# control_bdr.net
KiCad netlist of a schematic drawn in EAGLE
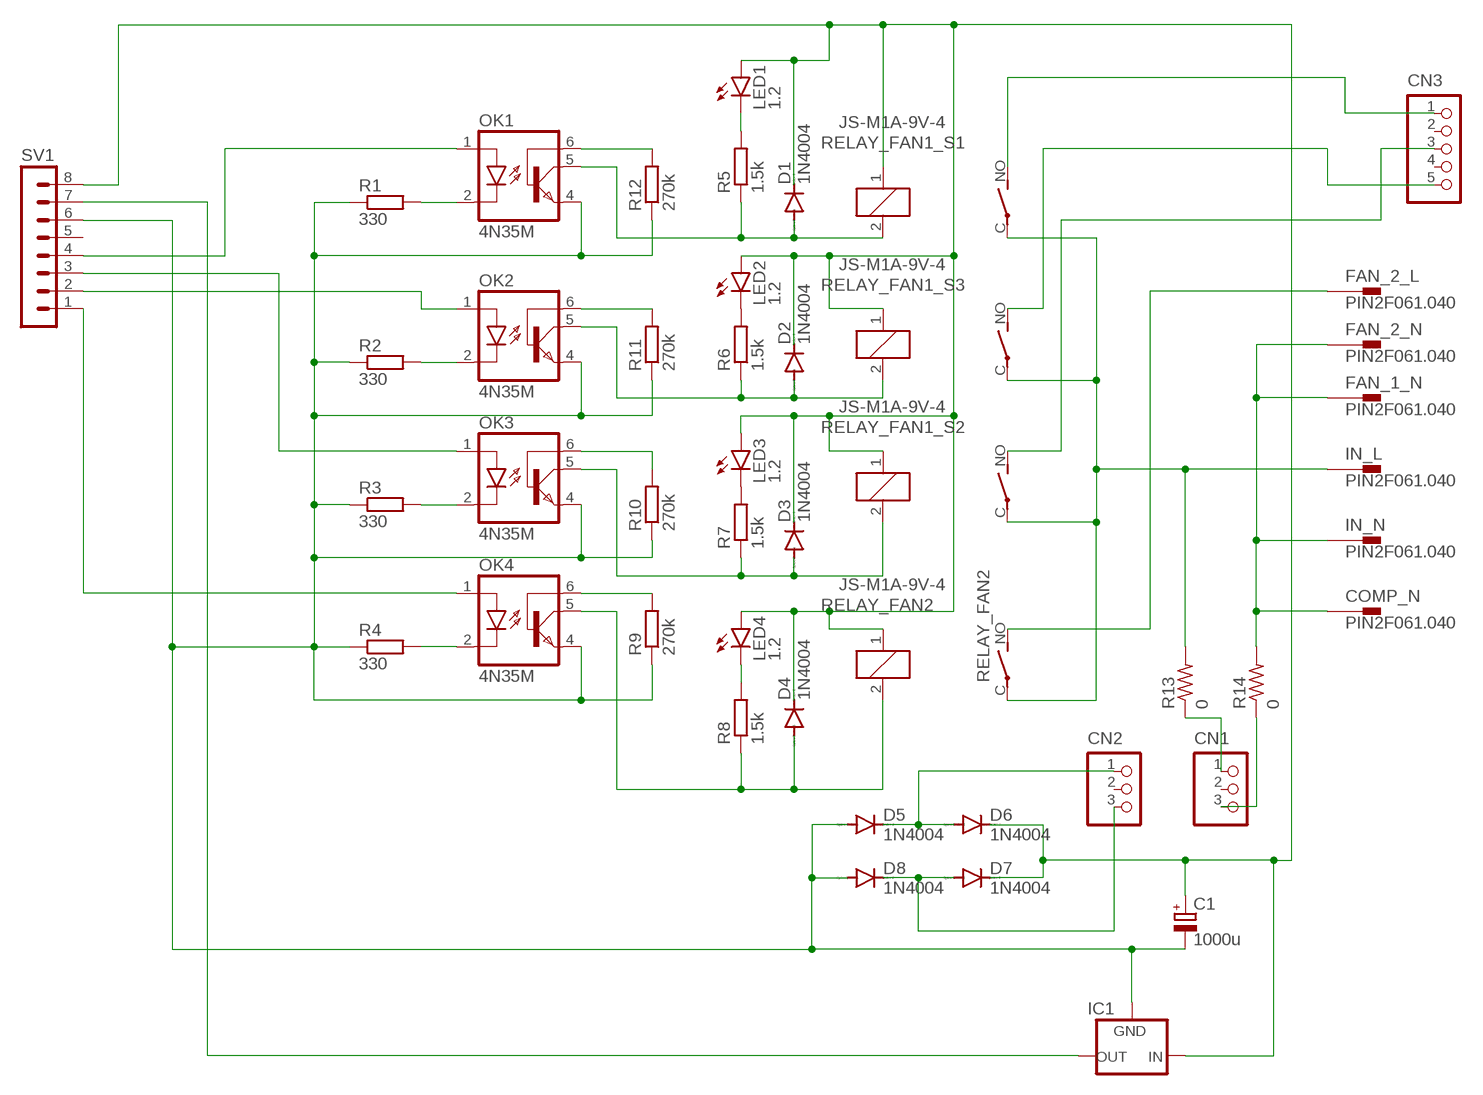
[diagram p0: schematic, sheet 1]

(export (version "E")
  (design (tool "Eeschema 10.0.6"))
  (components
    (comp (ref "C1")
      (value "1000u")
      (footprint "eagle-import:E3,5-10")
      (libsource (lib "eagle-import") (part "CPOL-EUE3.5-10"))
    )
    (comp (ref "CN1")
      (value "B3P-VH")
      (footprint "eagle-import:B3P-VH")
      (libsource (lib "eagle-import") (part "B3P-VH"))
    )
    (comp (ref "CN2")
      (value "B3B-XASK-1")
      (footprint "eagle-import:B3B-XASK-1")
      (libsource (lib "eagle-import") (part "B3B-XASK-1"))
    )
    (comp (ref "CN3")
      (value "B5P-VH")
      (footprint "eagle-import:B5P-VH")
      (libsource (lib "eagle-import") (part "B5P-VH"))
    )
    (comp (ref "COMP_N")
      (value "PIN2F061.040")
      (footprint "eagle-import:F061.040")
      (libsource (lib "eagle-import") (part "PIN2F061.040"))
    )
    (comp (ref "D1")
      (value "1N4004")
      (footprint "eagle-import:DO41-10")
      (libsource (lib "eagle-import") (part "1N4004"))
    )
    (comp (ref "D2")
      (value "1N4004")
      (footprint "eagle-import:DO41-10")
      (libsource (lib "eagle-import") (part "1N4004"))
    )
    (comp (ref "D3")
      (value "1N4004")
      (footprint "eagle-import:DO41-10")
      (libsource (lib "eagle-import") (part "1N4004"))
    )
    (comp (ref "D4")
      (value "1N4004")
      (footprint "eagle-import:DO41-10")
      (libsource (lib "eagle-import") (part "1N4004"))
    )
    (comp (ref "D5")
      (value "1N4004")
      (footprint "eagle-import:DO41-10")
      (libsource (lib "eagle-import") (part "1N4004"))
    )
    (comp (ref "D6")
      (value "1N4004")
      (footprint "eagle-import:DO41-10")
      (libsource (lib "eagle-import") (part "1N4004"))
    )
    (comp (ref "D7")
      (value "1N4004")
      (footprint "eagle-import:DO41-10")
      (libsource (lib "eagle-import") (part "1N4004"))
    )
    (comp (ref "D8")
      (value "1N4004")
      (footprint "eagle-import:DO41-10")
      (libsource (lib "eagle-import") (part "1N4004"))
    )
    (comp (ref "FAN_1_N")
      (value "PIN2F061.040")
      (footprint "eagle-import:F061.040")
      (libsource (lib "eagle-import") (part "PIN2F061.040"))
    )
    (comp (ref "FAN_2_L")
      (value "PIN2F061.040")
      (footprint "eagle-import:F061.040")
      (libsource (lib "eagle-import") (part "PIN2F061.040"))
    )
    (comp (ref "FAN_2_N")
      (value "PIN2F061.040")
      (footprint "eagle-import:F061.040")
      (libsource (lib "eagle-import") (part "PIN2F061.040"))
    )
    (comp (ref "IC1")
      (value "78XXL")
      (footprint "eagle-import:78XXL")
      (libsource (lib "eagle-import") (part "78XXL"))
    )
    (comp (ref "IN_L")
      (value "PIN2F061.040")
      (footprint "eagle-import:F061.040")
      (libsource (lib "eagle-import") (part "PIN2F061.040"))
    )
    (comp (ref "IN_N")
      (value "PIN2F061.040")
      (footprint "eagle-import:F061.040")
      (libsource (lib "eagle-import") (part "PIN2F061.040"))
    )
    (comp (ref "LED1")
      (value "1.2")
      (footprint "eagle-import:LED5MM")
      (libsource (lib "eagle-import") (part "LED5MM"))
    )
    (comp (ref "LED2")
      (value "1.2")
      (footprint "eagle-import:LED5MM")
      (libsource (lib "eagle-import") (part "LED5MM"))
    )
    (comp (ref "LED3")
      (value "1.2")
      (footprint "eagle-import:LED5MM")
      (libsource (lib "eagle-import") (part "LED5MM"))
    )
    (comp (ref "LED4")
      (value "1.2")
      (footprint "eagle-import:LED5MM")
      (libsource (lib "eagle-import") (part "LED5MM"))
    )
    (comp (ref "OK1")
      (value "4N35M")
      (footprint "eagle-import:DIL06")
      (fields (field (name "MPN") "4N35-M"))
      (libsource (lib "eagle-import") (part "4N?M35"))
    )
    (comp (ref "OK2")
      (value "4N35M")
      (footprint "eagle-import:DIL06")
      (fields (field (name "MPN") "4N35-M"))
      (libsource (lib "eagle-import") (part "4N?M35"))
    )
    (comp (ref "OK3")
      (value "4N35M")
      (footprint "eagle-import:DIL06")
      (fields (field (name "MPN") "4N35-M"))
      (libsource (lib "eagle-import") (part "4N?M35"))
    )
    (comp (ref "OK4")
      (value "4N35M")
      (footprint "eagle-import:DIL06")
      (fields (field (name "MPN") "4N35-M"))
      (libsource (lib "eagle-import") (part "4N?M35"))
    )
    (comp (ref "R1")
      (value "330")
      (footprint "eagle-import:0204_7")
      (libsource (lib "eagle-import") (part "R-EU_0204/7"))
    )
    (comp (ref "R2")
      (value "330")
      (footprint "eagle-import:0204_7")
      (libsource (lib "eagle-import") (part "R-EU_0204/7"))
    )
    (comp (ref "R3")
      (value "330")
      (footprint "eagle-import:0204_7")
      (libsource (lib "eagle-import") (part "R-EU_0204/7"))
    )
    (comp (ref "R4")
      (value "330")
      (footprint "eagle-import:0204_7")
      (libsource (lib "eagle-import") (part "R-EU_0204/7"))
    )
    (comp (ref "R5")
      (value "1.5k")
      (footprint "eagle-import:0204_7")
      (libsource (lib "eagle-import") (part "R-EU_0204/7"))
    )
    (comp (ref "R6")
      (value "1.5k")
      (footprint "eagle-import:0204_7")
      (libsource (lib "eagle-import") (part "R-EU_0204/7"))
    )
    (comp (ref "R7")
      (value "1.5k")
      (footprint "eagle-import:0204_7")
      (libsource (lib "eagle-import") (part "R-EU_0204/7"))
    )
    (comp (ref "R8")
      (value "1.5k")
      (footprint "eagle-import:0204_7")
      (libsource (lib "eagle-import") (part "R-EU_0204/7"))
    )
    (comp (ref "R9")
      (value "270k")
      (footprint "eagle-import:0204_7")
      (libsource (lib "eagle-import") (part "R-EU_0204/7"))
    )
    (comp (ref "R10")
      (value "270k")
      (footprint "eagle-import:0204_7")
      (libsource (lib "eagle-import") (part "R-EU_0204/7"))
    )
    (comp (ref "R11")
      (value "270k")
      (footprint "eagle-import:0204_7")
      (libsource (lib "eagle-import") (part "R-EU_0204/7"))
    )
    (comp (ref "R12")
      (value "270k")
      (footprint "eagle-import:0204_7")
      (libsource (lib "eagle-import") (part "R-EU_0204/7"))
    )
    (comp (ref "R13")
      (value "0")
      (footprint "eagle-import:0204V")
      (libsource (lib "eagle-import") (part "R-US_0204/2V"))
    )
    (comp (ref "R14")
      (value "0")
      (footprint "eagle-import:0204V")
      (libsource (lib "eagle-import") (part "R-US_0204/2V"))
    )
    (comp (ref "RELAY_FAN1_S1")
      (value "JS-M1A-9V-4")
      (footprint "eagle-import:JS-M1A")
      (libsource (lib "eagle-import") (part "JS-M1A-9V-4"))
    )
    (comp (ref "RELAY_FAN1_S2")
      (value "JS-M1A-9V-4")
      (footprint "eagle-import:JS-M1A")
      (libsource (lib "eagle-import") (part "JS-M1A-9V-4"))
    )
    (comp (ref "RELAY_FAN1_S3")
      (value "JS-M1A-9V-4")
      (footprint "eagle-import:JS-M1A")
      (libsource (lib "eagle-import") (part "JS-M1A-9V-4"))
    )
    (comp (ref "RELAY_FAN2")
      (value "JS-M1A-9V-4")
      (footprint "eagle-import:JS-M1A")
      (libsource (lib "eagle-import") (part "JS-M1A-9V-4"))
    )
    (comp (ref "SV1")
      (value "MA08-1")
      (footprint "eagle-import:MA08-1")
      (libsource (lib "eagle-import") (part "MA08-1"))
    )
  )
  (nets
    (net (code "1") (name "Net-(C1-Pad+)") (class "Default")
      (node (ref "C1") (pin "+") (pinfunction "+_+") (pintype "passive"))
      (node (ref "D1") (pin "C") (pinfunction "C_C") (pintype "passive"))
      (node (ref "D2") (pin "C") (pinfunction "C_C") (pintype "passive"))
      (node (ref "D3") (pin "C") (pinfunction "C_C") (pintype "passive"))
      (node (ref "D4") (pin "C") (pinfunction "C_C") (pintype "passive"))
      (node (ref "D6") (pin "C") (pinfunction "C_C") (pintype "passive"))
      (node (ref "D7") (pin "C") (pinfunction "C_C") (pintype "passive"))
      (node (ref "IC1") (pin "IN") (pinfunction "IN_IN") (pintype "input"))
      (node (ref "LED1") (pin "A") (pinfunction "A_A") (pintype "passive"))
      (node (ref "LED2") (pin "A") (pinfunction "A_A") (pintype "passive"))
      (node (ref "LED3") (pin "A") (pinfunction "A_A") (pintype "passive"))
      (node (ref "LED4") (pin "A") (pinfunction "A_A") (pintype "passive"))
      (node (ref "RELAY_FAN1_S1") (pin "1") (pinfunction "1_1") (pintype "passive"))
      (node (ref "RELAY_FAN1_S2") (pin "1") (pinfunction "1_1") (pintype "passive"))
      (node (ref "RELAY_FAN1_S3") (pin "1") (pinfunction "1_1") (pintype "passive"))
      (node (ref "RELAY_FAN2") (pin "1") (pinfunction "1_1") (pintype "passive"))
      (node (ref "SV1") (pin "8") (pinfunction "8_8") (pintype "passive"))
    )
    (net (code "2") (name "Net-(CN1-Pad1)") (class "Default")
      (node (ref "CN1") (pin "1") (pinfunction "1_1") (pintype "passive"))
      (node (ref "R13") (pin "1") (pinfunction "1_1") (pintype "passive"))
    )
    (net (code "3") (name "Net-(CN1-Pad3)") (class "Default")
      (node (ref "CN1") (pin "3") (pinfunction "3_3") (pintype "passive"))
      (node (ref "R14") (pin "1") (pinfunction "1_1") (pintype "passive"))
    )
    (net (code "4") (name "Net-(CN2-Pad1)") (class "Default")
      (node (ref "CN2") (pin "1") (pinfunction "1_1") (pintype "passive"))
      (node (ref "D5") (pin "C") (pinfunction "C_C") (pintype "passive"))
      (node (ref "D6") (pin "A") (pinfunction "A_A") (pintype "passive"))
    )
    (net (code "5") (name "Net-(CN2-Pad3)") (class "Default")
      (node (ref "CN2") (pin "3") (pinfunction "3_3") (pintype "passive"))
      (node (ref "D7") (pin "A") (pinfunction "A_A") (pintype "passive"))
      (node (ref "D8") (pin "C") (pinfunction "C_C") (pintype "passive"))
    )
    (net (code "6") (name "Net-(COMP_N-1-PadA1)") (class "Default")
      (node (ref "COMP_N") (pin "A1") (pinfunction "1_A1") (pintype "passive"))
      (node (ref "COMP_N") (pin "A2") (pinfunction "1_A2") (pintype "passive"))
      (node (ref "FAN_1_N") (pin "A1") (pinfunction "1_A1") (pintype "passive"))
      (node (ref "FAN_1_N") (pin "A2") (pinfunction "1_A2") (pintype "passive"))
      (node (ref "FAN_2_N") (pin "A1") (pinfunction "1_A1") (pintype "passive"))
      (node (ref "FAN_2_N") (pin "A2") (pinfunction "1_A2") (pintype "passive"))
      (node (ref "IN_N") (pin "A1") (pinfunction "1_A1") (pintype "passive"))
      (node (ref "IN_N") (pin "A2") (pinfunction "1_A2") (pintype "passive"))
      (node (ref "R14") (pin "2") (pinfunction "2_2") (pintype "passive"))
    )
    (net (code "7") (name "Net-(IC1-PadOUT)") (class "Default")
      (node (ref "IC1") (pin "OUT") (pinfunction "OUT_OUT") (pintype "passive"))
      (node (ref "SV1") (pin "7") (pinfunction "7_7") (pintype "passive"))
    )
    (net (code "8") (name "Net-(LED1-C)") (class "Default")
      (node (ref "LED1") (pin "K") (pinfunction "C_K") (pintype "passive"))
      (node (ref "R5") (pin "2") (pinfunction "2_2") (pintype "passive"))
    )
    (net (code "9") (name "Net-(LED2-C)") (class "Default")
      (node (ref "LED2") (pin "K") (pinfunction "C_K") (pintype "passive"))
      (node (ref "R6") (pin "2") (pinfunction "2_2") (pintype "passive"))
    )
    (net (code "10") (name "Net-(LED3-C)") (class "Default")
      (node (ref "LED3") (pin "K") (pinfunction "C_K") (pintype "passive"))
      (node (ref "R7") (pin "2") (pinfunction "2_2") (pintype "passive"))
    )
    (net (code "11") (name "Net-(LED4-C)") (class "Default")
      (node (ref "LED4") (pin "K") (pinfunction "C_K") (pintype "passive"))
      (node (ref "R8") (pin "2") (pinfunction "2_2") (pintype "passive"))
    )
    (net (code "12") (name "Net-(OK1-A)") (class "Default")
      (node (ref "OK1") (pin "1") (pinfunction "A_1") (pintype "passive"))
      (node (ref "SV1") (pin "4") (pinfunction "4_4") (pintype "passive"))
    )
    (net (code "13") (name "Net-(OK1-BAS)") (class "Default")
      (node (ref "OK1") (pin "6") (pinfunction "BAS_6") (pintype "passive"))
      (node (ref "R12") (pin "2") (pinfunction "2_2") (pintype "passive"))
    )
    (net (code "14") (name "Net-(OK1-C)") (class "Default")
      (node (ref "OK1") (pin "2") (pinfunction "C_2") (pintype "passive"))
      (node (ref "R1") (pin "2") (pinfunction "2_2") (pintype "passive"))
    )
    (net (code "15") (name "Net-(OK1-COL)") (class "Default")
      (node (ref "D1") (pin "A") (pinfunction "A_A") (pintype "passive"))
      (node (ref "OK1") (pin "5") (pinfunction "COL_5") (pintype "passive"))
      (node (ref "R5") (pin "1") (pinfunction "1_1") (pintype "passive"))
      (node (ref "RELAY_FAN1_S1") (pin "2") (pinfunction "2_2") (pintype "passive"))
    )
    (net (code "16") (name "Net-(OK1-EMI)") (class "Default")
      (node (ref "C1") (pin "-") (pinfunction "-_-") (pintype "passive"))
      (node (ref "D5") (pin "A") (pinfunction "A_A") (pintype "passive"))
      (node (ref "D8") (pin "A") (pinfunction "A_A") (pintype "passive"))
      (node (ref "IC1") (pin "GND") (pinfunction "GND_GND") (pintype "input"))
      (node (ref "OK1") (pin "4") (pinfunction "EMI_4") (pintype "passive"))
      (node (ref "OK2") (pin "4") (pinfunction "EMI_4") (pintype "passive"))
      (node (ref "OK3") (pin "4") (pinfunction "EMI_4") (pintype "passive"))
      (node (ref "OK4") (pin "4") (pinfunction "EMI_4") (pintype "passive"))
      (node (ref "R1") (pin "1") (pinfunction "1_1") (pintype "passive"))
      (node (ref "R10") (pin "1") (pinfunction "1_1") (pintype "passive"))
      (node (ref "R11") (pin "1") (pinfunction "1_1") (pintype "passive"))
      (node (ref "R12") (pin "1") (pinfunction "1_1") (pintype "passive"))
      (node (ref "R2") (pin "1") (pinfunction "1_1") (pintype "passive"))
      (node (ref "R3") (pin "1") (pinfunction "1_1") (pintype "passive"))
      (node (ref "R4") (pin "1") (pinfunction "1_1") (pintype "passive"))
      (node (ref "R9") (pin "1") (pinfunction "1_1") (pintype "passive"))
      (node (ref "SV1") (pin "6") (pinfunction "6_6") (pintype "passive"))
    )
    (net (code "17") (name "Net-(OK2-A)") (class "Default")
      (node (ref "OK2") (pin "1") (pinfunction "A_1") (pintype "passive"))
      (node (ref "SV1") (pin "2") (pinfunction "2_2") (pintype "passive"))
    )
    (net (code "18") (name "Net-(OK2-BAS)") (class "Default")
      (node (ref "OK2") (pin "6") (pinfunction "BAS_6") (pintype "passive"))
      (node (ref "R11") (pin "2") (pinfunction "2_2") (pintype "passive"))
    )
    (net (code "19") (name "Net-(OK2-C)") (class "Default")
      (node (ref "OK2") (pin "2") (pinfunction "C_2") (pintype "passive"))
      (node (ref "R2") (pin "2") (pinfunction "2_2") (pintype "passive"))
    )
    (net (code "20") (name "Net-(OK2-COL)") (class "Default")
      (node (ref "D2") (pin "A") (pinfunction "A_A") (pintype "passive"))
      (node (ref "OK2") (pin "5") (pinfunction "COL_5") (pintype "passive"))
      (node (ref "R6") (pin "1") (pinfunction "1_1") (pintype "passive"))
      (node (ref "RELAY_FAN1_S3") (pin "2") (pinfunction "2_2") (pintype "passive"))
    )
    (net (code "21") (name "Net-(OK3-A)") (class "Default")
      (node (ref "OK3") (pin "1") (pinfunction "A_1") (pintype "passive"))
      (node (ref "SV1") (pin "3") (pinfunction "3_3") (pintype "passive"))
    )
    (net (code "22") (name "Net-(OK3-BAS)") (class "Default")
      (node (ref "OK3") (pin "6") (pinfunction "BAS_6") (pintype "passive"))
      (node (ref "R10") (pin "2") (pinfunction "2_2") (pintype "passive"))
    )
    (net (code "23") (name "Net-(OK3-C)") (class "Default")
      (node (ref "OK3") (pin "2") (pinfunction "C_2") (pintype "passive"))
      (node (ref "R3") (pin "2") (pinfunction "2_2") (pintype "passive"))
    )
    (net (code "24") (name "Net-(OK3-COL)") (class "Default")
      (node (ref "D3") (pin "A") (pinfunction "A_A") (pintype "passive"))
      (node (ref "OK3") (pin "5") (pinfunction "COL_5") (pintype "passive"))
      (node (ref "R7") (pin "1") (pinfunction "1_1") (pintype "passive"))
      (node (ref "RELAY_FAN1_S2") (pin "2") (pinfunction "2_2") (pintype "passive"))
    )
    (net (code "25") (name "Net-(OK4-A)") (class "Default")
      (node (ref "OK4") (pin "1") (pinfunction "A_1") (pintype "passive"))
      (node (ref "SV1") (pin "1") (pinfunction "1_1") (pintype "passive"))
    )
    (net (code "26") (name "Net-(OK4-BAS)") (class "Default")
      (node (ref "OK4") (pin "6") (pinfunction "BAS_6") (pintype "passive"))
      (node (ref "R9") (pin "2") (pinfunction "2_2") (pintype "passive"))
    )
    (net (code "27") (name "Net-(OK4-C)") (class "Default")
      (node (ref "OK4") (pin "2") (pinfunction "C_2") (pintype "passive"))
      (node (ref "R4") (pin "2") (pinfunction "2_2") (pintype "passive"))
    )
    (net (code "28") (name "Net-(OK4-COL)") (class "Default")
      (node (ref "D4") (pin "A") (pinfunction "A_A") (pintype "passive"))
      (node (ref "OK4") (pin "5") (pinfunction "COL_5") (pintype "passive"))
      (node (ref "R8") (pin "1") (pinfunction "1_1") (pintype "passive"))
      (node (ref "RELAY_FAN2") (pin "2") (pinfunction "2_2") (pintype "passive"))
    )
    (net (code "29") (name "Net-(RELAY_FAN1_S1B-P)") (class "Default")
      (node (ref "IN_L") (pin "A1") (pinfunction "1_A1") (pintype "passive"))
      (node (ref "IN_L") (pin "A2") (pinfunction "1_A2") (pintype "passive"))
      (node (ref "R13") (pin "2") (pinfunction "2_2") (pintype "passive"))
      (node (ref "RELAY_FAN1_S1") (pin "C") (pinfunction "P_C") (pintype "passive"))
      (node (ref "RELAY_FAN1_S2") (pin "C") (pinfunction "P_C") (pintype "passive"))
      (node (ref "RELAY_FAN1_S3") (pin "C") (pinfunction "P_C") (pintype "passive"))
      (node (ref "RELAY_FAN2") (pin "C") (pinfunction "P_C") (pintype "passive"))
    )
    (net (code "30") (name "Net-(RELAY_FAN1_S1B-S)") (class "Default")
      (node (ref "CN3") (pin "1") (pinfunction "1_1") (pintype "passive"))
      (node (ref "RELAY_FAN1_S1") (pin "NO") (pinfunction "S_NO") (pintype "passive"))
    )
    (net (code "31") (name "Net-(RELAY_FAN1_S2B-S)") (class "Default")
      (node (ref "CN3") (pin "3") (pinfunction "3_3") (pintype "passive"))
      (node (ref "RELAY_FAN1_S2") (pin "NO") (pinfunction "S_NO") (pintype "passive"))
    )
    (net (code "32") (name "Net-(RELAY_FAN1_S3B-S)") (class "Default")
      (node (ref "CN3") (pin "5") (pinfunction "5_5") (pintype "passive"))
      (node (ref "RELAY_FAN1_S3") (pin "NO") (pinfunction "S_NO") (pintype "passive"))
    )
    (net (code "33") (name "Net-(RELAY_FAN2B-S)") (class "Default")
      (node (ref "FAN_2_L") (pin "A1") (pinfunction "1_A1") (pintype "passive"))
      (node (ref "FAN_2_L") (pin "A2") (pinfunction "1_A2") (pintype "passive"))
      (node (ref "RELAY_FAN2") (pin "NO") (pinfunction "S_NO") (pintype "passive"))
    )
    (net (code "34") (name "unconnected-(CN1-Pad2)") (class "Default")
      (node (ref "CN1") (pin "2") (pinfunction "2_2") (pintype "passive"))
    )
    (net (code "35") (name "unconnected-(CN2-Pad2)") (class "Default")
      (node (ref "CN2") (pin "2") (pinfunction "2_2") (pintype "passive"))
    )
    (net (code "36") (name "unconnected-(CN3-Pad2)") (class "Default")
      (node (ref "CN3") (pin "2") (pinfunction "2_2") (pintype "passive"))
    )
    (net (code "37") (name "unconnected-(CN3-Pad4)") (class "Default")
      (node (ref "CN3") (pin "4") (pinfunction "4_4") (pintype "passive"))
    )
    (net (code "38") (name "unconnected-(SV1-Pad5)") (class "Default")
      (node (ref "SV1") (pin "5") (pinfunction "5_5") (pintype "passive"))
    )
  )
)
